# SparkFun_SOIC8-DIP-Adapter.net
KiCad netlist of a schematic drawn in EAGLE
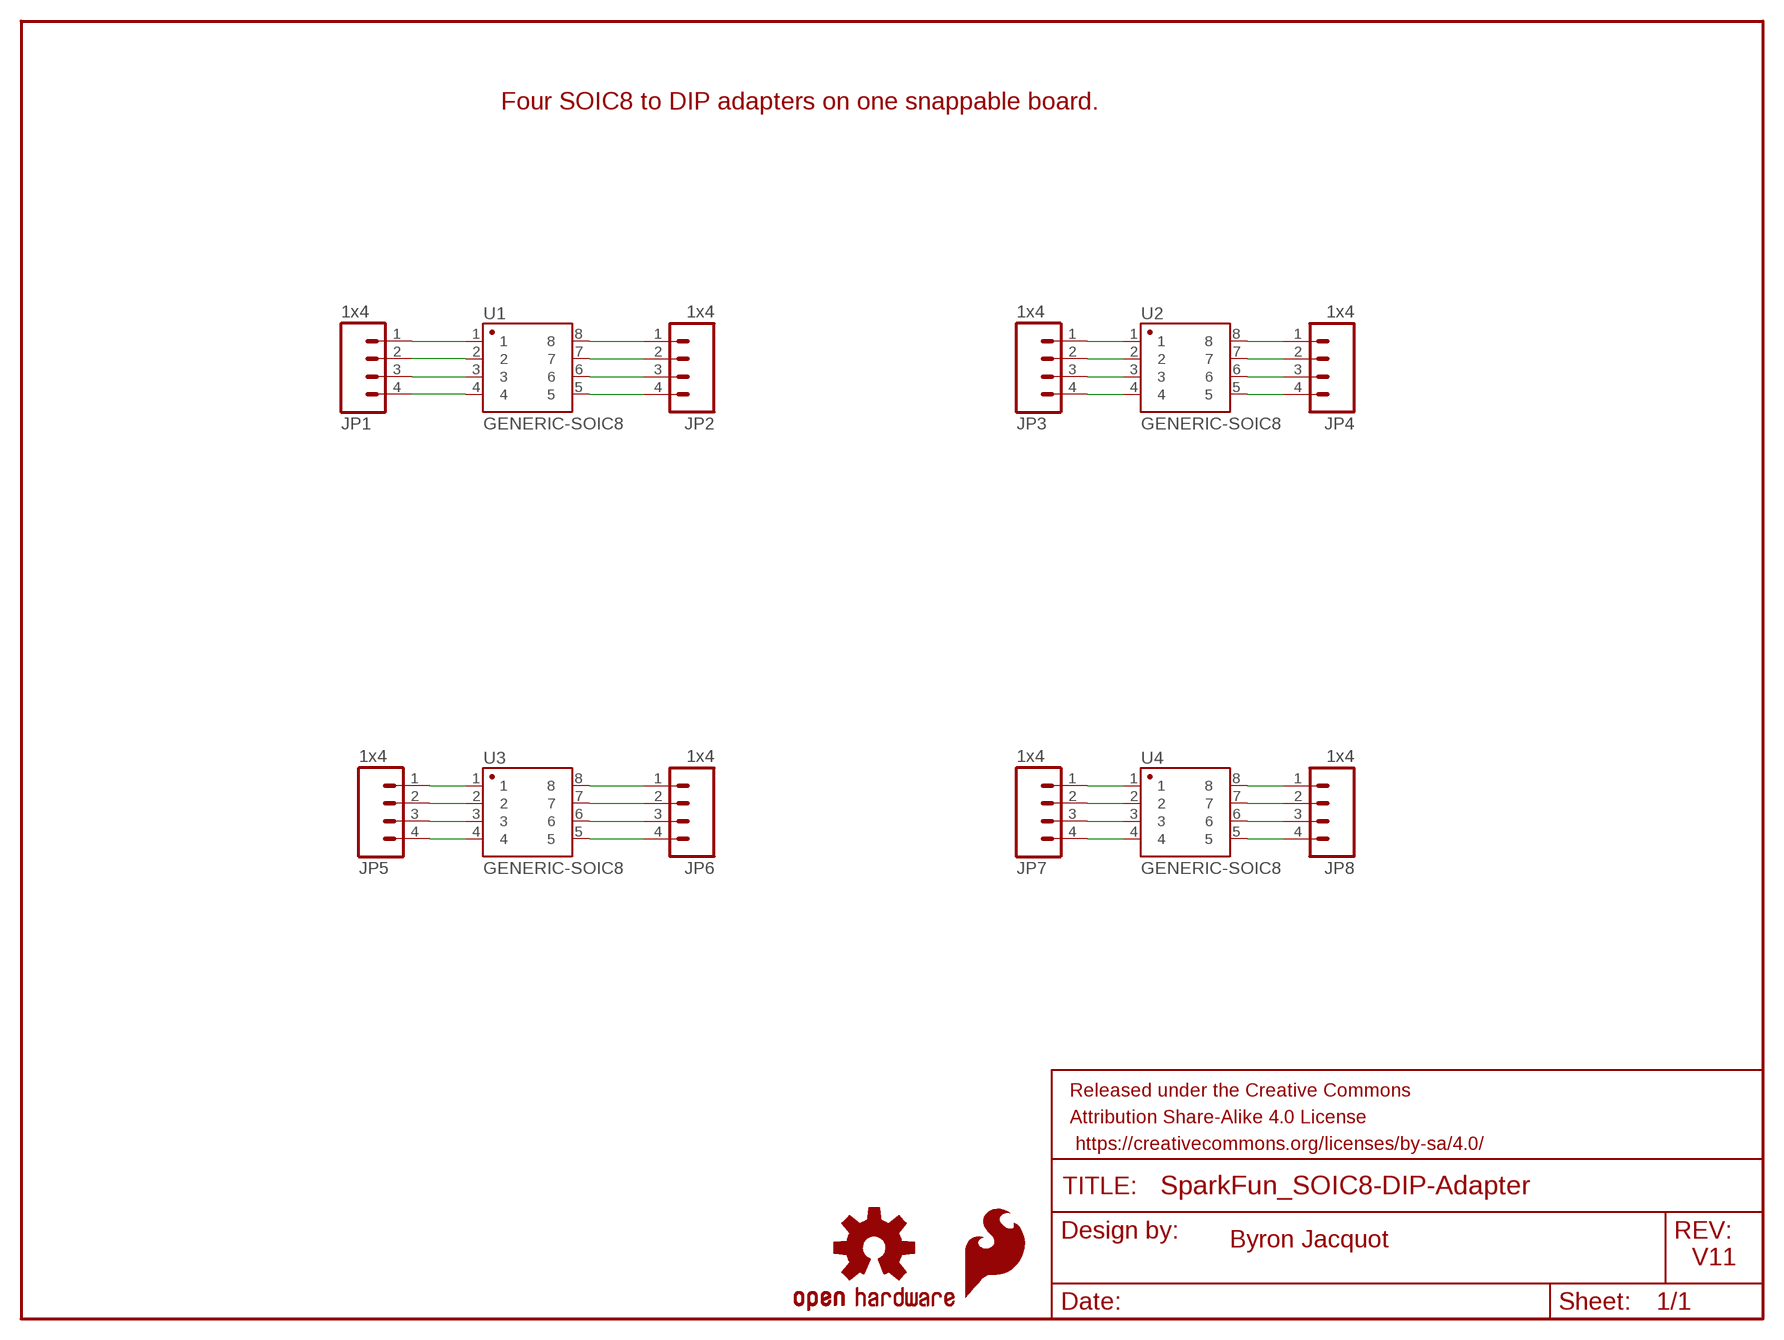
[diagram p0: schematic, sheet 1]

(export (version "E")
  (design (tool "Eeschema 10.0.6"))
  (components
    (comp (ref "FRAME1")
      (value "frame")
      (footprint "eagle-import:CREATIVE_COMMONS")
      (libsource (lib "eagle-import") (part "FRAME-LETTER"))
    )
    (comp (ref "JP1")
      (value "1x4")
      (footprint "eagle-import:1X04_NO_SILK")
      (libsource (lib "eagle-import") (part "M041X04_NO_SILK"))
    )
    (comp (ref "JP2")
      (value "1x4")
      (footprint "eagle-import:1X04_NO_SILK_ALL_ROUND")
      (libsource (lib "eagle-import") (part "M04NO_SILK_ALL_ROUND"))
    )
    (comp (ref "JP3")
      (value "1x4")
      (footprint "eagle-import:1X04_NO_SILK")
      (libsource (lib "eagle-import") (part "M041X04_NO_SILK"))
    )
    (comp (ref "JP4")
      (value "1x4")
      (footprint "eagle-import:1X04_NO_SILK_ALL_ROUND")
      (libsource (lib "eagle-import") (part "M04NO_SILK_ALL_ROUND"))
    )
    (comp (ref "JP5")
      (value "1x4")
      (footprint "eagle-import:1X04_NO_SILK")
      (libsource (lib "eagle-import") (part "M041X04_NO_SILK"))
    )
    (comp (ref "JP6")
      (value "1x4")
      (footprint "eagle-import:1X04_NO_SILK_ALL_ROUND")
      (libsource (lib "eagle-import") (part "M04NO_SILK_ALL_ROUND"))
    )
    (comp (ref "JP7")
      (value "1x4")
      (footprint "eagle-import:1X04_NO_SILK")
      (libsource (lib "eagle-import") (part "M041X04_NO_SILK"))
    )
    (comp (ref "JP8")
      (value "1x4")
      (footprint "eagle-import:1X04_NO_SILK_ALL_ROUND")
      (libsource (lib "eagle-import") (part "M04NO_SILK_ALL_ROUND"))
    )
    (comp (ref "LOGO1")
      (value "SFE_LOGO_FLAME.1_INCH")
      (footprint "eagle-import:SFE_LOGO_FLAME_.1")
      (libsource (lib "eagle-import") (part "SFE_LOGO_FLAME.1_INCH"))
    )
    (comp (ref "LOGO2")
      (value "OSHW-LOGOS")
      (footprint "eagle-import:OSHW-LOGO-S")
      (libsource (lib "eagle-import") (part "OSHW-LOGOS"))
    )
    (comp (ref "U1")
      (value "GENERIC-SOIC8")
      (footprint "eagle-import:SO08-UNIVERSAL")
      (libsource (lib "eagle-import") (part "GENERIC-SOIC8"))
    )
    (comp (ref "U2")
      (value "GENERIC-SOIC8")
      (footprint "eagle-import:SO08-UNIVERSAL")
      (libsource (lib "eagle-import") (part "GENERIC-SOIC8"))
    )
    (comp (ref "U3")
      (value "GENERIC-SOIC8")
      (footprint "eagle-import:SO08-UNIVERSAL")
      (libsource (lib "eagle-import") (part "GENERIC-SOIC8"))
    )
    (comp (ref "U4")
      (value "GENERIC-SOIC8")
      (footprint "eagle-import:SO08-UNIVERSAL")
      (libsource (lib "eagle-import") (part "GENERIC-SOIC8"))
    )
  )
  (nets
    (net (code "1") (name "Net-(JP1-Pad1)") (class "Default")
      (node (ref "JP1") (pin "1") (pinfunction "1_1") (pintype "passive"))
      (node (ref "U1") (pin "1") (pinfunction "1_1") (pintype "bidirectional"))
    )
    (net (code "2") (name "Net-(JP1-Pad2)") (class "Default")
      (node (ref "JP1") (pin "2") (pinfunction "2_2") (pintype "passive"))
      (node (ref "U1") (pin "2") (pinfunction "2_2") (pintype "bidirectional"))
    )
    (net (code "3") (name "Net-(JP1-Pad3)") (class "Default")
      (node (ref "JP1") (pin "3") (pinfunction "3_3") (pintype "passive"))
      (node (ref "U1") (pin "3") (pinfunction "3_3") (pintype "bidirectional"))
    )
    (net (code "4") (name "Net-(JP1-Pad4)") (class "Default")
      (node (ref "JP1") (pin "4") (pinfunction "4_4") (pintype "passive"))
      (node (ref "U1") (pin "4") (pinfunction "4_4") (pintype "bidirectional"))
    )
    (net (code "5") (name "Net-(JP2-Pad1)") (class "Default")
      (node (ref "JP2") (pin "1") (pinfunction "1_1") (pintype "passive"))
      (node (ref "U1") (pin "8") (pinfunction "8_8") (pintype "bidirectional"))
    )
    (net (code "6") (name "Net-(JP2-Pad2)") (class "Default")
      (node (ref "JP2") (pin "2") (pinfunction "2_2") (pintype "passive"))
      (node (ref "U1") (pin "7") (pinfunction "7_7") (pintype "bidirectional"))
    )
    (net (code "7") (name "Net-(JP2-Pad3)") (class "Default")
      (node (ref "JP2") (pin "3") (pinfunction "3_3") (pintype "passive"))
      (node (ref "U1") (pin "6") (pinfunction "6_6") (pintype "bidirectional"))
    )
    (net (code "8") (name "Net-(JP2-Pad4)") (class "Default")
      (node (ref "JP2") (pin "4") (pinfunction "4_4") (pintype "passive"))
      (node (ref "U1") (pin "5") (pinfunction "5_5") (pintype "bidirectional"))
    )
    (net (code "9") (name "Net-(JP3-Pad1)") (class "Default")
      (node (ref "JP3") (pin "1") (pinfunction "1_1") (pintype "passive"))
      (node (ref "U2") (pin "1") (pinfunction "1_1") (pintype "bidirectional"))
    )
    (net (code "10") (name "Net-(JP3-Pad2)") (class "Default")
      (node (ref "JP3") (pin "2") (pinfunction "2_2") (pintype "passive"))
      (node (ref "U2") (pin "2") (pinfunction "2_2") (pintype "bidirectional"))
    )
    (net (code "11") (name "Net-(JP3-Pad3)") (class "Default")
      (node (ref "JP3") (pin "3") (pinfunction "3_3") (pintype "passive"))
      (node (ref "U2") (pin "3") (pinfunction "3_3") (pintype "bidirectional"))
    )
    (net (code "12") (name "Net-(JP3-Pad4)") (class "Default")
      (node (ref "JP3") (pin "4") (pinfunction "4_4") (pintype "passive"))
      (node (ref "U2") (pin "4") (pinfunction "4_4") (pintype "bidirectional"))
    )
    (net (code "13") (name "Net-(JP4-Pad1)") (class "Default")
      (node (ref "JP4") (pin "1") (pinfunction "1_1") (pintype "passive"))
      (node (ref "U2") (pin "8") (pinfunction "8_8") (pintype "bidirectional"))
    )
    (net (code "14") (name "Net-(JP4-Pad2)") (class "Default")
      (node (ref "JP4") (pin "2") (pinfunction "2_2") (pintype "passive"))
      (node (ref "U2") (pin "7") (pinfunction "7_7") (pintype "bidirectional"))
    )
    (net (code "15") (name "Net-(JP4-Pad3)") (class "Default")
      (node (ref "JP4") (pin "3") (pinfunction "3_3") (pintype "passive"))
      (node (ref "U2") (pin "6") (pinfunction "6_6") (pintype "bidirectional"))
    )
    (net (code "16") (name "Net-(JP4-Pad4)") (class "Default")
      (node (ref "JP4") (pin "4") (pinfunction "4_4") (pintype "passive"))
      (node (ref "U2") (pin "5") (pinfunction "5_5") (pintype "bidirectional"))
    )
    (net (code "17") (name "Net-(JP5-Pad1)") (class "Default")
      (node (ref "JP5") (pin "1") (pinfunction "1_1") (pintype "passive"))
      (node (ref "U3") (pin "1") (pinfunction "1_1") (pintype "bidirectional"))
    )
    (net (code "18") (name "Net-(JP5-Pad2)") (class "Default")
      (node (ref "JP5") (pin "2") (pinfunction "2_2") (pintype "passive"))
      (node (ref "U3") (pin "2") (pinfunction "2_2") (pintype "bidirectional"))
    )
    (net (code "19") (name "Net-(JP5-Pad3)") (class "Default")
      (node (ref "JP5") (pin "3") (pinfunction "3_3") (pintype "passive"))
      (node (ref "U3") (pin "3") (pinfunction "3_3") (pintype "bidirectional"))
    )
    (net (code "20") (name "Net-(JP5-Pad4)") (class "Default")
      (node (ref "JP5") (pin "4") (pinfunction "4_4") (pintype "passive"))
      (node (ref "U3") (pin "4") (pinfunction "4_4") (pintype "bidirectional"))
    )
    (net (code "21") (name "Net-(JP6-Pad1)") (class "Default")
      (node (ref "JP6") (pin "1") (pinfunction "1_1") (pintype "passive"))
      (node (ref "U3") (pin "8") (pinfunction "8_8") (pintype "bidirectional"))
    )
    (net (code "22") (name "Net-(JP6-Pad2)") (class "Default")
      (node (ref "JP6") (pin "2") (pinfunction "2_2") (pintype "passive"))
      (node (ref "U3") (pin "7") (pinfunction "7_7") (pintype "bidirectional"))
    )
    (net (code "23") (name "Net-(JP6-Pad3)") (class "Default")
      (node (ref "JP6") (pin "3") (pinfunction "3_3") (pintype "passive"))
      (node (ref "U3") (pin "6") (pinfunction "6_6") (pintype "bidirectional"))
    )
    (net (code "24") (name "Net-(JP6-Pad4)") (class "Default")
      (node (ref "JP6") (pin "4") (pinfunction "4_4") (pintype "passive"))
      (node (ref "U3") (pin "5") (pinfunction "5_5") (pintype "bidirectional"))
    )
    (net (code "25") (name "Net-(JP7-Pad1)") (class "Default")
      (node (ref "JP7") (pin "1") (pinfunction "1_1") (pintype "passive"))
      (node (ref "U4") (pin "1") (pinfunction "1_1") (pintype "bidirectional"))
    )
    (net (code "26") (name "Net-(JP7-Pad2)") (class "Default")
      (node (ref "JP7") (pin "2") (pinfunction "2_2") (pintype "passive"))
      (node (ref "U4") (pin "2") (pinfunction "2_2") (pintype "bidirectional"))
    )
    (net (code "27") (name "Net-(JP7-Pad3)") (class "Default")
      (node (ref "JP7") (pin "3") (pinfunction "3_3") (pintype "passive"))
      (node (ref "U4") (pin "3") (pinfunction "3_3") (pintype "bidirectional"))
    )
    (net (code "28") (name "Net-(JP7-Pad4)") (class "Default")
      (node (ref "JP7") (pin "4") (pinfunction "4_4") (pintype "passive"))
      (node (ref "U4") (pin "4") (pinfunction "4_4") (pintype "bidirectional"))
    )
    (net (code "29") (name "Net-(JP8-Pad1)") (class "Default")
      (node (ref "JP8") (pin "1") (pinfunction "1_1") (pintype "passive"))
      (node (ref "U4") (pin "8") (pinfunction "8_8") (pintype "bidirectional"))
    )
    (net (code "30") (name "Net-(JP8-Pad2)") (class "Default")
      (node (ref "JP8") (pin "2") (pinfunction "2_2") (pintype "passive"))
      (node (ref "U4") (pin "7") (pinfunction "7_7") (pintype "bidirectional"))
    )
    (net (code "31") (name "Net-(JP8-Pad3)") (class "Default")
      (node (ref "JP8") (pin "3") (pinfunction "3_3") (pintype "passive"))
      (node (ref "U4") (pin "6") (pinfunction "6_6") (pintype "bidirectional"))
    )
    (net (code "32") (name "Net-(JP8-Pad4)") (class "Default")
      (node (ref "JP8") (pin "4") (pinfunction "4_4") (pintype "passive"))
      (node (ref "U4") (pin "5") (pinfunction "5_5") (pintype "bidirectional"))
    )
  )
)
